# zx81_kbd_v0_4.net
KiCad netlist of a schematic drawn in EAGLE
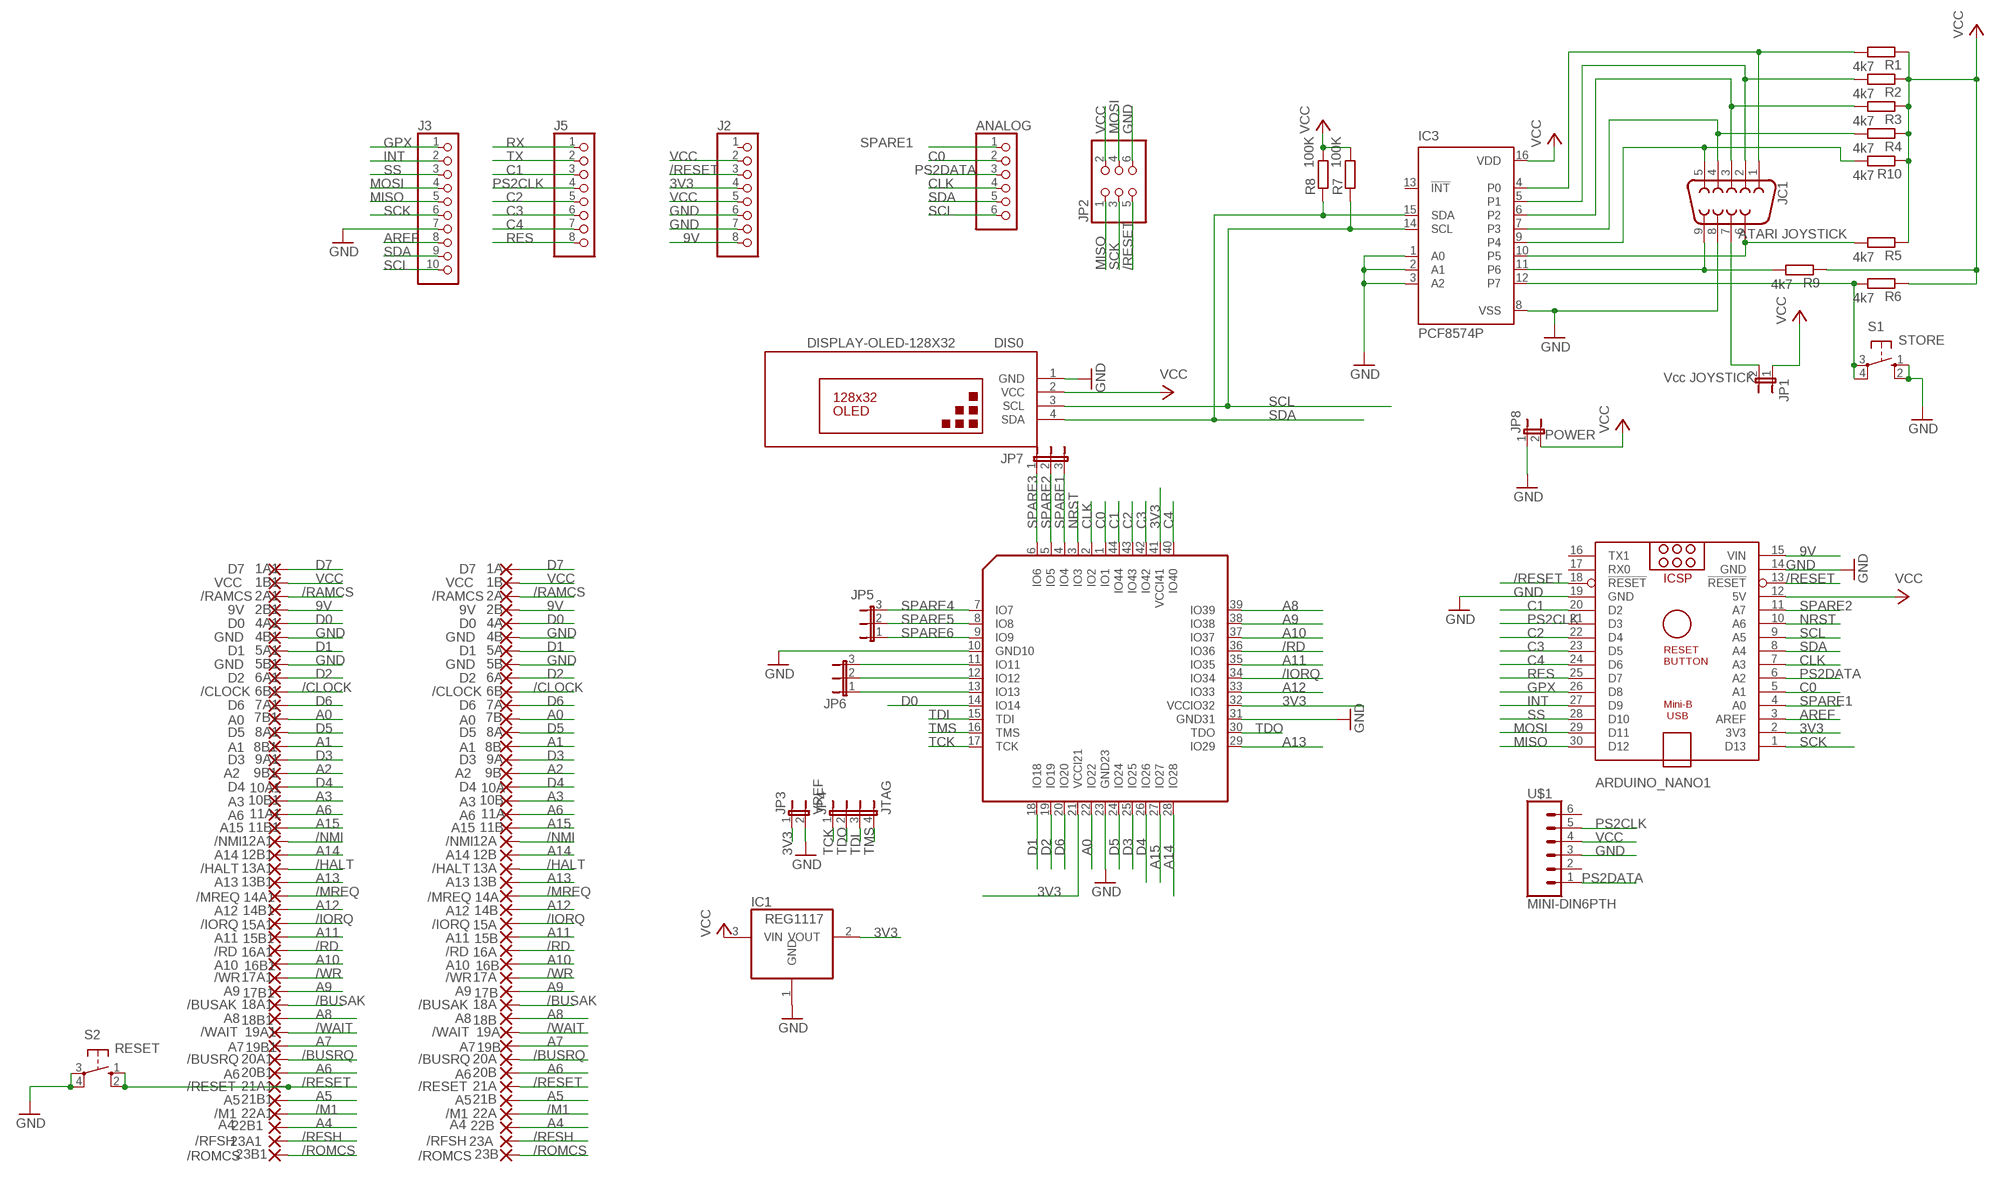
[diagram p0: schematic, sheet 1]

(export (version "E")
  (design (tool "Eeschema 10.0.6"))
  (components
    (comp (ref "1A")
      (value "D7")
      (footprint "eagle-import:EDGEPIN")
      (libsource (lib "eagle-import") (part "SMD2EDGEPIN"))
    )
    (comp (ref "1A1")
      (value "D7")
      (footprint "eagle-import:EDGEPIN")
      (libsource (lib "eagle-import") (part "SMD2EDGEPIN"))
    )
    (comp (ref "1B")
      (value "VCC")
      (footprint "eagle-import:EDGEPIN")
      (libsource (lib "eagle-import") (part "SMD2EDGEPIN"))
    )
    (comp (ref "1B1")
      (value "VCC")
      (footprint "eagle-import:EDGEPIN")
      (libsource (lib "eagle-import") (part "SMD2EDGEPIN"))
    )
    (comp (ref "2A")
      (value "/RAMCS")
      (footprint "eagle-import:EDGEPIN")
      (libsource (lib "eagle-import") (part "SMD2EDGEPIN"))
    )
    (comp (ref "2A1")
      (value "/RAMCS")
      (footprint "eagle-import:EDGEPIN")
      (libsource (lib "eagle-import") (part "SMD2EDGEPIN"))
    )
    (comp (ref "2B")
      (value "9V")
      (footprint "eagle-import:EDGEPIN")
      (libsource (lib "eagle-import") (part "SMD2EDGEPIN"))
    )
    (comp (ref "2B1")
      (value "9V")
      (footprint "eagle-import:EDGEPIN")
      (libsource (lib "eagle-import") (part "SMD2EDGEPIN"))
    )
    (comp (ref "4A")
      (value "D0")
      (footprint "eagle-import:EDGEPIN")
      (libsource (lib "eagle-import") (part "SMD2EDGEPIN"))
    )
    (comp (ref "4A1")
      (value "D0")
      (footprint "eagle-import:EDGEPIN")
      (libsource (lib "eagle-import") (part "SMD2EDGEPIN"))
    )
    (comp (ref "4B")
      (value "GND")
      (footprint "eagle-import:EDGEPIN")
      (libsource (lib "eagle-import") (part "SMD2EDGEPIN"))
    )
    (comp (ref "4B1")
      (value "GND")
      (footprint "eagle-import:EDGEPIN")
      (libsource (lib "eagle-import") (part "SMD2EDGEPIN"))
    )
    (comp (ref "5A")
      (value "D1")
      (footprint "eagle-import:EDGEPIN")
      (libsource (lib "eagle-import") (part "SMD2EDGEPIN"))
    )
    (comp (ref "5A1")
      (value "D1")
      (footprint "eagle-import:EDGEPIN")
      (libsource (lib "eagle-import") (part "SMD2EDGEPIN"))
    )
    (comp (ref "5B")
      (value "GND")
      (footprint "eagle-import:EDGEPIN")
      (libsource (lib "eagle-import") (part "SMD2EDGEPIN"))
    )
    (comp (ref "5B1")
      (value "GND")
      (footprint "eagle-import:EDGEPIN")
      (libsource (lib "eagle-import") (part "SMD2EDGEPIN"))
    )
    (comp (ref "6A")
      (value "D2")
      (footprint "eagle-import:EDGEPIN")
      (libsource (lib "eagle-import") (part "SMD2EDGEPIN"))
    )
    (comp (ref "6A1")
      (value "D2")
      (footprint "eagle-import:EDGEPIN")
      (libsource (lib "eagle-import") (part "SMD2EDGEPIN"))
    )
    (comp (ref "6B")
      (value "/CLOCK")
      (footprint "eagle-import:EDGEPIN")
      (libsource (lib "eagle-import") (part "SMD2EDGEPIN"))
    )
    (comp (ref "6B1")
      (value "/CLOCK")
      (footprint "eagle-import:EDGEPIN")
      (libsource (lib "eagle-import") (part "SMD2EDGEPIN"))
    )
    (comp (ref "7A")
      (value "D6")
      (footprint "eagle-import:EDGEPIN")
      (libsource (lib "eagle-import") (part "SMD2EDGEPIN"))
    )
    (comp (ref "7A1")
      (value "D6")
      (footprint "eagle-import:EDGEPIN")
      (libsource (lib "eagle-import") (part "SMD2EDGEPIN"))
    )
    (comp (ref "7B")
      (value "A0")
      (footprint "eagle-import:EDGEPIN")
      (libsource (lib "eagle-import") (part "SMD2EDGEPIN"))
    )
    (comp (ref "7B1")
      (value "A0")
      (footprint "eagle-import:EDGEPIN")
      (libsource (lib "eagle-import") (part "SMD2EDGEPIN"))
    )
    (comp (ref "8A")
      (value "D5")
      (footprint "eagle-import:EDGEPIN")
      (libsource (lib "eagle-import") (part "SMD2EDGEPIN"))
    )
    (comp (ref "8A1")
      (value "D5")
      (footprint "eagle-import:EDGEPIN")
      (libsource (lib "eagle-import") (part "SMD2EDGEPIN"))
    )
    (comp (ref "8B")
      (value "A1")
      (footprint "eagle-import:EDGEPIN")
      (libsource (lib "eagle-import") (part "SMD2EDGEPIN"))
    )
    (comp (ref "8B1")
      (value "A1")
      (footprint "eagle-import:EDGEPIN")
      (libsource (lib "eagle-import") (part "SMD2EDGEPIN"))
    )
    (comp (ref "9A")
      (value "D3")
      (footprint "eagle-import:EDGEPIN")
      (libsource (lib "eagle-import") (part "SMD2EDGEPIN"))
    )
    (comp (ref "9A1")
      (value "D3")
      (footprint "eagle-import:EDGEPIN")
      (libsource (lib "eagle-import") (part "SMD2EDGEPIN"))
    )
    (comp (ref "9B")
      (value "A2")
      (footprint "eagle-import:EDGEPIN")
      (libsource (lib "eagle-import") (part "SMD2EDGEPIN"))
    )
    (comp (ref "9B1")
      (value "A2")
      (footprint "eagle-import:EDGEPIN")
      (libsource (lib "eagle-import") (part "SMD2EDGEPIN"))
    )
    (comp (ref "10A")
      (value "D4")
      (footprint "eagle-import:EDGEPIN")
      (libsource (lib "eagle-import") (part "SMD2EDGEPIN"))
    )
    (comp (ref "10A1")
      (value "D4")
      (footprint "eagle-import:EDGEPIN")
      (libsource (lib "eagle-import") (part "SMD2EDGEPIN"))
    )
    (comp (ref "10B")
      (value "A3")
      (footprint "eagle-import:EDGEPIN")
      (libsource (lib "eagle-import") (part "SMD2EDGEPIN"))
    )
    (comp (ref "10B1")
      (value "A3")
      (footprint "eagle-import:EDGEPIN")
      (libsource (lib "eagle-import") (part "SMD2EDGEPIN"))
    )
    (comp (ref "11A")
      (value "A6")
      (footprint "eagle-import:EDGEPIN")
      (libsource (lib "eagle-import") (part "SMD2EDGEPIN"))
    )
    (comp (ref "11A1")
      (value "A6")
      (footprint "eagle-import:EDGEPIN")
      (libsource (lib "eagle-import") (part "SMD2EDGEPIN"))
    )
    (comp (ref "11B")
      (value "A15")
      (footprint "eagle-import:EDGEPIN")
      (libsource (lib "eagle-import") (part "SMD2EDGEPIN"))
    )
    (comp (ref "11B1")
      (value "A15")
      (footprint "eagle-import:EDGEPIN")
      (libsource (lib "eagle-import") (part "SMD2EDGEPIN"))
    )
    (comp (ref "12A")
      (value "/NMI")
      (footprint "eagle-import:EDGEPIN")
      (libsource (lib "eagle-import") (part "SMD2EDGEPIN"))
    )
    (comp (ref "12A1")
      (value "/NMI")
      (footprint "eagle-import:EDGEPIN")
      (libsource (lib "eagle-import") (part "SMD2EDGEPIN"))
    )
    (comp (ref "12B")
      (value "A14")
      (footprint "eagle-import:EDGEPIN")
      (libsource (lib "eagle-import") (part "SMD2EDGEPIN"))
    )
    (comp (ref "12B1")
      (value "A14")
      (footprint "eagle-import:EDGEPIN")
      (libsource (lib "eagle-import") (part "SMD2EDGEPIN"))
    )
    (comp (ref "13A")
      (value "/HALT")
      (footprint "eagle-import:EDGEPIN")
      (libsource (lib "eagle-import") (part "SMD2EDGEPIN"))
    )
    (comp (ref "13A1")
      (value "/HALT")
      (footprint "eagle-import:EDGEPIN")
      (libsource (lib "eagle-import") (part "SMD2EDGEPIN"))
    )
    (comp (ref "13B")
      (value "A13")
      (footprint "eagle-import:EDGEPIN")
      (libsource (lib "eagle-import") (part "SMD2EDGEPIN"))
    )
    (comp (ref "13B1")
      (value "A13")
      (footprint "eagle-import:EDGEPIN")
      (libsource (lib "eagle-import") (part "SMD2EDGEPIN"))
    )
    (comp (ref "14A")
      (value "/MREQ")
      (footprint "eagle-import:EDGEPIN")
      (libsource (lib "eagle-import") (part "SMD2EDGEPIN"))
    )
    (comp (ref "14A1")
      (value "/MREQ")
      (footprint "eagle-import:EDGEPIN")
      (libsource (lib "eagle-import") (part "SMD2EDGEPIN"))
    )
    (comp (ref "14B")
      (value "A12")
      (footprint "eagle-import:EDGEPIN")
      (libsource (lib "eagle-import") (part "SMD2EDGEPIN"))
    )
    (comp (ref "14B1")
      (value "A12")
      (footprint "eagle-import:EDGEPIN")
      (libsource (lib "eagle-import") (part "SMD2EDGEPIN"))
    )
    (comp (ref "15A")
      (value "/IORQ")
      (footprint "eagle-import:EDGEPIN")
      (libsource (lib "eagle-import") (part "SMD2EDGEPIN"))
    )
    (comp (ref "15A1")
      (value "/IORQ")
      (footprint "eagle-import:EDGEPIN")
      (libsource (lib "eagle-import") (part "SMD2EDGEPIN"))
    )
    (comp (ref "15B")
      (value "A11")
      (footprint "eagle-import:EDGEPIN")
      (libsource (lib "eagle-import") (part "SMD2EDGEPIN"))
    )
    (comp (ref "15B1")
      (value "A11")
      (footprint "eagle-import:EDGEPIN")
      (libsource (lib "eagle-import") (part "SMD2EDGEPIN"))
    )
    (comp (ref "16A")
      (value "/RD")
      (footprint "eagle-import:EDGEPIN")
      (libsource (lib "eagle-import") (part "SMD2EDGEPIN"))
    )
    (comp (ref "16A1")
      (value "/RD")
      (footprint "eagle-import:EDGEPIN")
      (libsource (lib "eagle-import") (part "SMD2EDGEPIN"))
    )
    (comp (ref "16B")
      (value "A10")
      (footprint "eagle-import:EDGEPIN")
      (libsource (lib "eagle-import") (part "SMD2EDGEPIN"))
    )
    (comp (ref "16B1")
      (value "A10")
      (footprint "eagle-import:EDGEPIN")
      (libsource (lib "eagle-import") (part "SMD2EDGEPIN"))
    )
    (comp (ref "17A")
      (value "/WR")
      (footprint "eagle-import:EDGEPIN")
      (libsource (lib "eagle-import") (part "SMD2EDGEPIN"))
    )
    (comp (ref "17A1")
      (value "/WR")
      (footprint "eagle-import:EDGEPIN")
      (libsource (lib "eagle-import") (part "SMD2EDGEPIN"))
    )
    (comp (ref "17B")
      (value "A9")
      (footprint "eagle-import:EDGEPIN")
      (libsource (lib "eagle-import") (part "SMD2EDGEPIN"))
    )
    (comp (ref "17B1")
      (value "A9")
      (footprint "eagle-import:EDGEPIN")
      (libsource (lib "eagle-import") (part "SMD2EDGEPIN"))
    )
    (comp (ref "18A")
      (value "/BUSAK")
      (footprint "eagle-import:EDGEPIN")
      (libsource (lib "eagle-import") (part "SMD2EDGEPIN"))
    )
    (comp (ref "18A1")
      (value "/BUSAK")
      (footprint "eagle-import:EDGEPIN")
      (libsource (lib "eagle-import") (part "SMD2EDGEPIN"))
    )
    (comp (ref "18B")
      (value "A8")
      (footprint "eagle-import:EDGEPIN")
      (libsource (lib "eagle-import") (part "SMD2EDGEPIN"))
    )
    (comp (ref "18B1")
      (value "A8")
      (footprint "eagle-import:EDGEPIN")
      (libsource (lib "eagle-import") (part "SMD2EDGEPIN"))
    )
    (comp (ref "19A")
      (value "/WAIT")
      (footprint "eagle-import:EDGEPIN")
      (libsource (lib "eagle-import") (part "SMD2EDGEPIN"))
    )
    (comp (ref "19A1")
      (value "/WAIT")
      (footprint "eagle-import:EDGEPIN")
      (libsource (lib "eagle-import") (part "SMD2EDGEPIN"))
    )
    (comp (ref "19B")
      (value "A7")
      (footprint "eagle-import:EDGEPIN")
      (libsource (lib "eagle-import") (part "SMD2EDGEPIN"))
    )
    (comp (ref "19B1")
      (value "A7")
      (footprint "eagle-import:EDGEPIN")
      (libsource (lib "eagle-import") (part "SMD2EDGEPIN"))
    )
    (comp (ref "20A")
      (value "/BUSRQ")
      (footprint "eagle-import:EDGEPIN")
      (libsource (lib "eagle-import") (part "SMD2EDGEPIN"))
    )
    (comp (ref "20A1")
      (value "/BUSRQ")
      (footprint "eagle-import:EDGEPIN")
      (libsource (lib "eagle-import") (part "SMD2EDGEPIN"))
    )
    (comp (ref "20B")
      (value "A6")
      (footprint "eagle-import:EDGEPIN")
      (libsource (lib "eagle-import") (part "SMD2EDGEPIN"))
    )
    (comp (ref "20B1")
      (value "A6")
      (footprint "eagle-import:EDGEPIN")
      (libsource (lib "eagle-import") (part "SMD2EDGEPIN"))
    )
    (comp (ref "21A")
      (value "/RESET")
      (footprint "eagle-import:EDGEPIN")
      (libsource (lib "eagle-import") (part "SMD2EDGEPIN"))
    )
    (comp (ref "21A1")
      (value "/RESET")
      (footprint "eagle-import:EDGEPIN")
      (libsource (lib "eagle-import") (part "SMD2EDGEPIN"))
    )
    (comp (ref "21B")
      (value "A5")
      (footprint "eagle-import:EDGEPIN")
      (libsource (lib "eagle-import") (part "SMD2EDGEPIN"))
    )
    (comp (ref "21B1")
      (value "A5")
      (footprint "eagle-import:EDGEPIN")
      (libsource (lib "eagle-import") (part "SMD2EDGEPIN"))
    )
    (comp (ref "22A")
      (value "/M1")
      (footprint "eagle-import:EDGEPIN")
      (libsource (lib "eagle-import") (part "SMD2EDGEPIN"))
    )
    (comp (ref "22A1")
      (value "/M1")
      (footprint "eagle-import:EDGEPIN")
      (libsource (lib "eagle-import") (part "SMD2EDGEPIN"))
    )
    (comp (ref "22B")
      (value "A4")
      (footprint "eagle-import:EDGEPIN")
      (libsource (lib "eagle-import") (part "SMD2EDGEPIN"))
    )
    (comp (ref "22B1")
      (value "A4")
      (footprint "eagle-import:EDGEPIN")
      (libsource (lib "eagle-import") (part "SMD2EDGEPIN"))
    )
    (comp (ref "23A")
      (value "/RFSH")
      (footprint "eagle-import:EDGEPIN")
      (libsource (lib "eagle-import") (part "SMD2EDGEPIN"))
    )
    (comp (ref "23A1")
      (value "/RFSH")
      (footprint "eagle-import:EDGEPIN")
      (libsource (lib "eagle-import") (part "SMD2EDGEPIN"))
    )
    (comp (ref "23B")
      (value "/ROMCS")
      (footprint "eagle-import:EDGEPIN")
      (libsource (lib "eagle-import") (part "SMD2EDGEPIN"))
    )
    (comp (ref "23B1")
      (value "/ROMCS")
      (footprint "eagle-import:EDGEPIN")
      (libsource (lib "eagle-import") (part "SMD2EDGEPIN"))
    )
    (comp (ref "ANALOG")
      (value "PINHD-1X6")
      (footprint "eagle-import:1X06")
      (libsource (lib "eagle-import") (part "PINHD-1X6"))
    )
    (comp (ref "ARDUINO_NANO1")
      (value "ARDUINO_NANO")
      (footprint "eagle-import:ARDUINO_NANO")
      (libsource (lib "eagle-import") (part "ARDUINO_NANO"))
    )
    (comp (ref "DIS0")
      (value "DISPLAY-OLED-128X32")
      (footprint "eagle-import:DISPLAY-OLED-128X32")
      (libsource (lib "eagle-import") (part "DISPLAY-OLED-128X32"))
    )
    (comp (ref "IC1")
      (value "REG1117")
      (footprint "eagle-import:SOT223")
      (libsource (lib "eagle-import") (part "REG1117"))
    )
    (comp (ref "IC3")
      (value "PCF8574P")
      (footprint "eagle-import:DIL16")
      (fields (field (name "MPN") "PCF8574PN"))
      (libsource (lib "eagle-import") (part "PCF8574P"))
    )
    (comp (ref "J2")
      (value "PINHD-1X8")
      (footprint "eagle-import:1X08")
      (libsource (lib "eagle-import") (part "PINHD-1X8"))
    )
    (comp (ref "J3")
      (value "PINHD-1X10")
      (footprint "eagle-import:1X10")
      (libsource (lib "eagle-import") (part "PINHD-1X10"))
    )
    (comp (ref "J5")
      (value "PINHD-1X8")
      (footprint "eagle-import:1X08")
      (libsource (lib "eagle-import") (part "PINHD-1X8"))
    )
    (comp (ref "JC1")
      (value "ATARI JOYSTICK")
      (footprint "eagle-import:DB9_MALE")
      (libsource (lib "eagle-import") (part "DB9MALE"))
    )
    (comp (ref "JP1")
      (value "Vcc JOYSTICK")
      (footprint "eagle-import:JP1")
      (libsource (lib "eagle-import") (part "JP1E"))
    )
    (comp (ref "JP2")
      (value "PINHD-2X3")
      (footprint "eagle-import:2X03")
      (libsource (lib "eagle-import") (part "PINHD-2X3"))
    )
    (comp (ref "JP3")
      (value "VREF")
      (footprint "eagle-import:JP1")
      (libsource (lib "eagle-import") (part "jumper_35741532_JP1E"))
    )
    (comp (ref "JP4")
      (value "JTAG")
      (footprint "eagle-import:JP4")
      (libsource (lib "eagle-import") (part "JP4E"))
    )
    (comp (ref "JP5")
      (value "JP2E")
      (footprint "eagle-import:JP2")
      (libsource (lib "eagle-import") (part "JP2E"))
    )
    (comp (ref "JP6")
      (value "JP2E")
      (footprint "eagle-import:JP2")
      (libsource (lib "eagle-import") (part "JP2E"))
    )
    (comp (ref "JP7")
      (value "JP2E")
      (footprint "eagle-import:JP2")
      (libsource (lib "eagle-import") (part "JP2E"))
    )
    (comp (ref "JP8")
      (value "POWER")
      (footprint "eagle-import:JP1")
      (libsource (lib "eagle-import") (part "JP1E"))
    )
    (comp (ref "R1")
      (value "4k7")
      (footprint "eagle-import:0204_7")
      (libsource (lib "eagle-import") (part "R-EU_0204/7"))
    )
    (comp (ref "R2")
      (value "4k7")
      (footprint "eagle-import:0204_7")
      (libsource (lib "eagle-import") (part "R-EU_0204/7"))
    )
    (comp (ref "R3")
      (value "4k7")
      (footprint "eagle-import:0204_7")
      (libsource (lib "eagle-import") (part "R-EU_0204/7"))
    )
    (comp (ref "R4")
      (value "4k7")
      (footprint "eagle-import:0204_7")
      (libsource (lib "eagle-import") (part "R-EU_0204/7"))
    )
    (comp (ref "R5")
      (value "4k7")
      (footprint "eagle-import:0204_7")
      (libsource (lib "eagle-import") (part "R-EU_0204/7"))
    )
    (comp (ref "R6")
      (value "4k7")
      (footprint "eagle-import:0204_7")
      (libsource (lib "eagle-import") (part "R-EU_0204/7"))
    )
    (comp (ref "R7")
      (value "100K")
      (footprint "eagle-import:0204_7")
      (libsource (lib "eagle-import") (part "R-EU_0204/7"))
    )
    (comp (ref "R8")
      (value "100K")
      (footprint "eagle-import:0204_7")
      (libsource (lib "eagle-import") (part "R-EU_0204/7"))
    )
    (comp (ref "R9")
      (value "4k7")
      (footprint "eagle-import:0204_7")
      (libsource (lib "eagle-import") (part "R-EU_0204/7"))
    )
    (comp (ref "R10")
      (value "4k7")
      (footprint "eagle-import:0204_7")
      (libsource (lib "eagle-import") (part "R-EU_0204/7"))
    )
    (comp (ref "S1")
      (value "STORE")
      (footprint "eagle-import:B3F-10XX_11MM")
      (libsource (lib "eagle-import") (part "10-XX11MM"))
    )
    (comp (ref "S2")
      (value "RESET")
      (footprint "eagle-import:B3F-10XX_11MM")
      (libsource (lib "eagle-import") (part "10-XX11MM"))
    )
    (comp (ref "U$1")
      (value "MINI-DIN6PTH")
      (footprint "eagle-import:MINI-DIN6")
      (libsource (lib "eagle-import") (part "MINI-DIN6PTH"))
    )
    (comp (ref "XC95CPLD")
      (value "XC9572PLC")
      (footprint "eagle-import:3M44")
      (libsource (lib "eagle-import") (part "XC9572PLC"))
    )
  )
  (nets
    (net (code "1") (name "/3V3") (class "Default")
      (node (ref "ARDUINO_NANO1") (pin "2") (pinfunction "3V3_2") (pintype "output"))
      (node (ref "IC1") (pin "2") (pinfunction "VOUT_2") (pintype "output"))
      (node (ref "J2") (pin "4") (pinfunction "4_4") (pintype "passive"))
      (node (ref "JP3") (pin "1") (pinfunction "1_1") (pintype "passive"))
      (node (ref "XC95CPLD") (pin "21") (pinfunction "VCCI21_21") (pintype "power_in"))
      (node (ref "XC95CPLD") (pin "32") (pinfunction "VCCIO32_32") (pintype "power_in"))
      (node (ref "XC95CPLD") (pin "41") (pinfunction "VCCI41_41") (pintype "power_in"))
    )
    (net (code "2") (name "/9V") (class "Default")
      (node (ref "2B") (pin "1") (pinfunction "P_1") (pintype "passive"))
      (node (ref "2B1") (pin "1") (pinfunction "P_1") (pintype "passive"))
      (node (ref "ARDUINO_NANO1") (pin "15") (pinfunction "VIN_15") (pintype "power_in"))
      (node (ref "J2") (pin "8") (pinfunction "8_8") (pintype "passive"))
    )
    (net (code "3") (name "/A0") (class "Default")
      (node (ref "7B") (pin "1") (pinfunction "P_1") (pintype "passive"))
      (node (ref "7B1") (pin "1") (pinfunction "P_1") (pintype "passive"))
      (node (ref "XC95CPLD") (pin "22") (pinfunction "IO22_22") (pintype "bidirectional"))
    )
    (net (code "4") (name "/A1") (class "Default")
      (node (ref "8B") (pin "1") (pinfunction "P_1") (pintype "passive"))
      (node (ref "8B1") (pin "1") (pinfunction "P_1") (pintype "passive"))
    )
    (net (code "5") (name "/A2") (class "Default")
      (node (ref "9B") (pin "1") (pinfunction "P_1") (pintype "passive"))
      (node (ref "9B1") (pin "1") (pinfunction "P_1") (pintype "passive"))
    )
    (net (code "6") (name "/A3") (class "Default")
      (node (ref "10B") (pin "1") (pinfunction "P_1") (pintype "passive"))
      (node (ref "10B1") (pin "1") (pinfunction "P_1") (pintype "passive"))
    )
    (net (code "7") (name "/A4") (class "Default")
      (node (ref "22B") (pin "1") (pinfunction "P_1") (pintype "passive"))
      (node (ref "22B1") (pin "1") (pinfunction "P_1") (pintype "passive"))
    )
    (net (code "8") (name "/A5") (class "Default")
      (node (ref "21B") (pin "1") (pinfunction "P_1") (pintype "passive"))
      (node (ref "21B1") (pin "1") (pinfunction "P_1") (pintype "passive"))
    )
    (net (code "9") (name "/A6") (class "Default")
      (node (ref "11A") (pin "1") (pinfunction "P_1") (pintype "passive"))
      (node (ref "11A1") (pin "1") (pinfunction "P_1") (pintype "passive"))
      (node (ref "20B") (pin "1") (pinfunction "P_1") (pintype "passive"))
      (node (ref "20B1") (pin "1") (pinfunction "P_1") (pintype "passive"))
    )
    (net (code "10") (name "/A7") (class "Default")
      (node (ref "19B") (pin "1") (pinfunction "P_1") (pintype "passive"))
      (node (ref "19B1") (pin "1") (pinfunction "P_1") (pintype "passive"))
    )
    (net (code "11") (name "/A8") (class "Default")
      (node (ref "18B") (pin "1") (pinfunction "P_1") (pintype "passive"))
      (node (ref "18B1") (pin "1") (pinfunction "P_1") (pintype "passive"))
      (node (ref "XC95CPLD") (pin "39") (pinfunction "IO39_39") (pintype "bidirectional"))
    )
    (net (code "12") (name "/A9") (class "Default")
      (node (ref "17B") (pin "1") (pinfunction "P_1") (pintype "passive"))
      (node (ref "17B1") (pin "1") (pinfunction "P_1") (pintype "passive"))
      (node (ref "XC95CPLD") (pin "38") (pinfunction "IO38_38") (pintype "bidirectional"))
    )
    (net (code "13") (name "/A10") (class "Default")
      (node (ref "16B") (pin "1") (pinfunction "P_1") (pintype "passive"))
      (node (ref "16B1") (pin "1") (pinfunction "P_1") (pintype "passive"))
      (node (ref "XC95CPLD") (pin "37") (pinfunction "IO37_37") (pintype "bidirectional"))
    )
    (net (code "14") (name "/A11") (class "Default")
      (node (ref "15B") (pin "1") (pinfunction "P_1") (pintype "passive"))
      (node (ref "15B1") (pin "1") (pinfunction "P_1") (pintype "passive"))
      (node (ref "XC95CPLD") (pin "35") (pinfunction "IO35_35") (pintype "bidirectional"))
    )
    (net (code "15") (name "/A12") (class "Default")
      (node (ref "14B") (pin "1") (pinfunction "P_1") (pintype "passive"))
      (node (ref "14B1") (pin "1") (pinfunction "P_1") (pintype "passive"))
      (node (ref "XC95CPLD") (pin "33") (pinfunction "IO33_33") (pintype "bidirectional"))
    )
    (net (code "16") (name "/A13") (class "Default")
      (node (ref "13B") (pin "1") (pinfunction "P_1") (pintype "passive"))
      (node (ref "13B1") (pin "1") (pinfunction "P_1") (pintype "passive"))
      (node (ref "XC95CPLD") (pin "29") (pinfunction "IO29_29") (pintype "bidirectional"))
    )
    (net (code "17") (name "/A14") (class "Default")
      (node (ref "12B") (pin "1") (pinfunction "P_1") (pintype "passive"))
      (node (ref "12B1") (pin "1") (pinfunction "P_1") (pintype "passive"))
      (node (ref "XC95CPLD") (pin "28") (pinfunction "IO28_28") (pintype "bidirectional"))
    )
    (net (code "18") (name "/A15") (class "Default")
      (node (ref "11B") (pin "1") (pinfunction "P_1") (pintype "passive"))
      (node (ref "11B1") (pin "1") (pinfunction "P_1") (pintype "passive"))
      (node (ref "XC95CPLD") (pin "27") (pinfunction "IO27_27") (pintype "bidirectional"))
    )
    (net (code "19") (name "/AREF") (class "Default")
      (node (ref "ARDUINO_NANO1") (pin "3") (pinfunction "AREF_3") (pintype "input"))
      (node (ref "J3") (pin "8") (pinfunction "8_8") (pintype "passive"))
    )
    (net (code "20") (name "/C0") (class "Default")
      (node (ref "ANALOG") (pin "2") (pinfunction "2_2") (pintype "passive"))
      (node (ref "ARDUINO_NANO1") (pin "5") (pinfunction "A1_5") (pintype "bidirectional"))
      (node (ref "XC95CPLD") (pin "1") (pinfunction "IO1_1") (pintype "bidirectional"))
    )
    (net (code "21") (name "/C1") (class "Default")
      (node (ref "ARDUINO_NANO1") (pin "20") (pinfunction "D2_20") (pintype "bidirectional"))
      (node (ref "J5") (pin "3") (pinfunction "3_3") (pintype "passive"))
      (node (ref "XC95CPLD") (pin "44") (pinfunction "IO44_44") (pintype "bidirectional"))
    )
    (net (code "22") (name "/C2") (class "Default")
      (node (ref "ARDUINO_NANO1") (pin "22") (pinfunction "D4_22") (pintype "bidirectional"))
      (node (ref "J5") (pin "5") (pinfunction "5_5") (pintype "passive"))
      (node (ref "XC95CPLD") (pin "43") (pinfunction "IO43_43") (pintype "bidirectional"))
    )
    (net (code "23") (name "/C3") (class "Default")
      (node (ref "ARDUINO_NANO1") (pin "23") (pinfunction "D5_23") (pintype "bidirectional"))
      (node (ref "J5") (pin "6") (pinfunction "6_6") (pintype "passive"))
      (node (ref "XC95CPLD") (pin "42") (pinfunction "IO42_42") (pintype "bidirectional"))
    )
    (net (code "24") (name "/C4") (class "Default")
      (node (ref "ARDUINO_NANO1") (pin "24") (pinfunction "D6_24") (pintype "bidirectional"))
      (node (ref "J5") (pin "7") (pinfunction "7_7") (pintype "passive"))
      (node (ref "XC95CPLD") (pin "40") (pinfunction "IO40_40") (pintype "bidirectional"))
    )
    (net (code "25") (name "/CLK") (class "Default")
      (node (ref "ANALOG") (pin "4") (pinfunction "4_4") (pintype "passive"))
      (node (ref "ARDUINO_NANO1") (pin "7") (pinfunction "A3_7") (pintype "bidirectional"))
      (node (ref "XC95CPLD") (pin "2") (pinfunction "IO2_2") (pintype "bidirectional"))
    )
    (net (code "26") (name "/D0") (class "Default")
      (node (ref "4A") (pin "1") (pinfunction "P_1") (pintype "passive"))
      (node (ref "4A1") (pin "1") (pinfunction "P_1") (pintype "passive"))
      (node (ref "XC95CPLD") (pin "14") (pinfunction "IO14_14") (pintype "bidirectional"))
    )
    (net (code "27") (name "/D1") (class "Default")
      (node (ref "5A") (pin "1") (pinfunction "P_1") (pintype "passive"))
      (node (ref "5A1") (pin "1") (pinfunction "P_1") (pintype "passive"))
      (node (ref "XC95CPLD") (pin "18") (pinfunction "IO18_18") (pintype "bidirectional"))
    )
    (net (code "28") (name "/D2") (class "Default")
      (node (ref "6A") (pin "1") (pinfunction "P_1") (pintype "passive"))
      (node (ref "6A1") (pin "1") (pinfunction "P_1") (pintype "passive"))
      (node (ref "XC95CPLD") (pin "19") (pinfunction "IO19_19") (pintype "bidirectional"))
    )
    (net (code "29") (name "/D3") (class "Default")
      (node (ref "9A") (pin "1") (pinfunction "P_1") (pintype "passive"))
      (node (ref "9A1") (pin "1") (pinfunction "P_1") (pintype "passive"))
      (node (ref "XC95CPLD") (pin "25") (pinfunction "IO25_25") (pintype "bidirectional"))
    )
    (net (code "30") (name "/D4") (class "Default")
      (node (ref "10A") (pin "1") (pinfunction "P_1") (pintype "passive"))
      (node (ref "10A1") (pin "1") (pinfunction "P_1") (pintype "passive"))
      (node (ref "XC95CPLD") (pin "26") (pinfunction "IO26_26") (pintype "bidirectional"))
    )
    (net (code "31") (name "/D5") (class "Default")
      (node (ref "8A") (pin "1") (pinfunction "P_1") (pintype "passive"))
      (node (ref "8A1") (pin "1") (pinfunction "P_1") (pintype "passive"))
      (node (ref "XC95CPLD") (pin "24") (pinfunction "IO24_24") (pintype "bidirectional"))
    )
    (net (code "32") (name "/D6") (class "Default")
      (node (ref "7A") (pin "1") (pinfunction "P_1") (pintype "passive"))
      (node (ref "7A1") (pin "1") (pinfunction "P_1") (pintype "passive"))
      (node (ref "XC95CPLD") (pin "20") (pinfunction "IO20_20") (pintype "bidirectional"))
    )
    (net (code "33") (name "/D7") (class "Default")
      (node (ref "1A") (pin "1") (pinfunction "P_1") (pintype "passive"))
      (node (ref "1A1") (pin "1") (pinfunction "P_1") (pintype "passive"))
    )
    (net (code "34") (name "/GPX") (class "Default")
      (node (ref "ARDUINO_NANO1") (pin "26") (pinfunction "D8_26") (pintype "bidirectional"))
      (node (ref "J3") (pin "1") (pinfunction "1_1") (pintype "passive"))
    )
    (net (code "35") (name "/INT") (class "Default")
      (node (ref "ARDUINO_NANO1") (pin "27") (pinfunction "D9_27") (pintype "bidirectional"))
      (node (ref "J3") (pin "2") (pinfunction "2_2") (pintype "passive"))
    )
    (net (code "36") (name "/MISO") (class "Default")
      (node (ref "ARDUINO_NANO1") (pin "30") (pinfunction "D12_30") (pintype "bidirectional"))
      (node (ref "J3") (pin "5") (pinfunction "5_5") (pintype "passive"))
      (node (ref "JP2") (pin "1") (pinfunction "1_1") (pintype "passive"))
    )
    (net (code "37") (name "/MOSI") (class "Default")
      (node (ref "ARDUINO_NANO1") (pin "29") (pinfunction "D11_29") (pintype "bidirectional"))
      (node (ref "J3") (pin "4") (pinfunction "4_4") (pintype "passive"))
      (node (ref "JP2") (pin "4") (pinfunction "4_4") (pintype "passive"))
    )
    (net (code "38") (name "/NRST") (class "Default")
      (node (ref "ARDUINO_NANO1") (pin "10") (pinfunction "A6_10") (pintype "bidirectional"))
      (node (ref "XC95CPLD") (pin "3") (pinfunction "IO3_3") (pintype "bidirectional"))
    )
    (net (code "39") (name "/PS2CLK") (class "Default")
      (node (ref "ARDUINO_NANO1") (pin "21") (pinfunction "D3_21") (pintype "bidirectional"))
      (node (ref "J5") (pin "4") (pinfunction "4_4") (pintype "passive"))
      (node (ref "U$1") (pin "5") (pinfunction "5_5") (pintype "passive"))
    )
    (net (code "40") (name "/PS2DATA") (class "Default")
      (node (ref "ANALOG") (pin "3") (pinfunction "3_3") (pintype "passive"))
      (node (ref "ARDUINO_NANO1") (pin "6") (pinfunction "A2_6") (pintype "bidirectional"))
      (node (ref "U$1") (pin "1") (pinfunction "1_1") (pintype "passive"))
    )
    (net (code "41") (name "/RES") (class "Default")
      (node (ref "ARDUINO_NANO1") (pin "25") (pinfunction "D7_25") (pintype "bidirectional"))
      (node (ref "J5") (pin "8") (pinfunction "8_8") (pintype "passive"))
    )
    (net (code "42") (name "/RX") (class "Default")
      (node (ref "J5") (pin "1") (pinfunction "1_1") (pintype "passive"))
    )
    (net (code "43") (name "/SCK") (class "Default")
      (node (ref "ARDUINO_NANO1") (pin "1") (pinfunction "D13_1") (pintype "bidirectional"))
      (node (ref "J3") (pin "6") (pinfunction "6_6") (pintype "passive"))
      (node (ref "JP2") (pin "3") (pinfunction "3_3") (pintype "passive"))
    )
    (net (code "44") (name "/SCL") (class "Default")
      (node (ref "ANALOG") (pin "6") (pinfunction "6_6") (pintype "passive"))
      (node (ref "ARDUINO_NANO1") (pin "9") (pinfunction "A5_9") (pintype "bidirectional"))
      (node (ref "DIS0") (pin "3") (pinfunction "SCL_3") (pintype "bidirectional"))
      (node (ref "IC3") (pin "14") (pinfunction "SCL_14") (pintype "input"))
      (node (ref "J3") (pin "10") (pinfunction "10_10") (pintype "passive"))
      (node (ref "R7") (pin "1") (pinfunction "1_1") (pintype "passive"))
    )
    (net (code "45") (name "/SDA") (class "Default")
      (node (ref "ANALOG") (pin "5") (pinfunction "5_5") (pintype "passive"))
      (node (ref "ARDUINO_NANO1") (pin "8") (pinfunction "A4_8") (pintype "bidirectional"))
      (node (ref "DIS0") (pin "4") (pinfunction "SDA_4") (pintype "bidirectional"))
      (node (ref "IC3") (pin "15") (pinfunction "SDA_15") (pintype "bidirectional"))
      (node (ref "J3") (pin "9") (pinfunction "9_9") (pintype "passive"))
      (node (ref "R8") (pin "1") (pinfunction "1_1") (pintype "passive"))
    )
    (net (code "46") (name "/SPARE1") (class "Default")
      (node (ref "ANALOG") (pin "1") (pinfunction "1_1") (pintype "passive"))
      (node (ref "ARDUINO_NANO1") (pin "4") (pinfunction "A0_4") (pintype "bidirectional"))
      (node (ref "JP7") (pin "3") (pinfunction "3_3") (pintype "passive"))
      (node (ref "XC95CPLD") (pin "4") (pinfunction "IO4_4") (pintype "bidirectional"))
    )
    (net (code "47") (name "/SPARE2") (class "Default")
      (node (ref "ARDUINO_NANO1") (pin "11") (pinfunction "A7_11") (pintype "bidirectional"))
      (node (ref "JP7") (pin "2") (pinfunction "2_2") (pintype "passive"))
      (node (ref "XC95CPLD") (pin "5") (pinfunction "IO5_5") (pintype "bidirectional"))
    )
    (net (code "48") (name "/SPARE3") (class "Default")
      (node (ref "JP7") (pin "1") (pinfunction "1_1") (pintype "passive"))
      (node (ref "XC95CPLD") (pin "6") (pinfunction "IO6_6") (pintype "bidirectional"))
    )
    (net (code "49") (name "/SPARE4") (class "Default")
      (node (ref "JP5") (pin "3") (pinfunction "3_3") (pintype "passive"))
      (node (ref "XC95CPLD") (pin "7") (pinfunction "IO7_7") (pintype "bidirectional"))
    )
    (net (code "50") (name "/SPARE5") (class "Default")
      (node (ref "JP5") (pin "2") (pinfunction "2_2") (pintype "passive"))
      (node (ref "XC95CPLD") (pin "8") (pinfunction "IO8_8") (pintype "bidirectional"))
    )
    (net (code "51") (name "/SPARE6") (class "Default")
      (node (ref "JP5") (pin "1") (pinfunction "1_1") (pintype "passive"))
      (node (ref "XC95CPLD") (pin "9") (pinfunction "IO9_9") (pintype "bidirectional"))
    )
    (net (code "52") (name "/SS") (class "Default")
      (node (ref "ARDUINO_NANO1") (pin "28") (pinfunction "D10_28") (pintype "bidirectional"))
      (node (ref "J3") (pin "3") (pinfunction "3_3") (pintype "passive"))
    )
    (net (code "53") (name "/TCK") (class "Default")
      (node (ref "JP4") (pin "1") (pinfunction "1_1") (pintype "passive"))
      (node (ref "XC95CPLD") (pin "17") (pinfunction "TCK_17") (pintype "passive"))
    )
    (net (code "54") (name "/TDI") (class "Default")
      (node (ref "JP4") (pin "3") (pinfunction "3_3") (pintype "passive"))
      (node (ref "XC95CPLD") (pin "15") (pinfunction "TDI_15") (pintype "passive"))
    )
    (net (code "55") (name "/TDO") (class "Default")
      (node (ref "JP4") (pin "2") (pinfunction "2_2") (pintype "passive"))
      (node (ref "XC95CPLD") (pin "30") (pinfunction "TDO_30") (pintype "passive"))
    )
    (net (code "56") (name "/TMS") (class "Default")
      (node (ref "JP4") (pin "4") (pinfunction "4_4") (pintype "passive"))
      (node (ref "XC95CPLD") (pin "16") (pinfunction "TMS_16") (pintype "passive"))
    )
    (net (code "57") (name "/TX") (class "Default")
      (node (ref "J5") (pin "2") (pinfunction "2_2") (pintype "passive"))
    )
    (net (code "58") (name "/{slash}BUSAK") (class "Default")
      (node (ref "18A") (pin "1") (pinfunction "P_1") (pintype "passive"))
      (node (ref "18A1") (pin "1") (pinfunction "P_1") (pintype "passive"))
    )
    (net (code "59") (name "/{slash}BUSRQ") (class "Default")
      (node (ref "20A") (pin "1") (pinfunction "P_1") (pintype "passive"))
      (node (ref "20A1") (pin "1") (pinfunction "P_1") (pintype "passive"))
    )
    (net (code "60") (name "/{slash}CLOCK") (class "Default")
      (node (ref "6B") (pin "1") (pinfunction "P_1") (pintype "passive"))
      (node (ref "6B1") (pin "1") (pinfunction "P_1") (pintype "passive"))
    )
    (net (code "61") (name "/{slash}HALT") (class "Default")
      (node (ref "13A") (pin "1") (pinfunction "P_1") (pintype "passive"))
      (node (ref "13A1") (pin "1") (pinfunction "P_1") (pintype "passive"))
    )
    (net (code "62") (name "/{slash}IORQ") (class "Default")
      (node (ref "15A") (pin "1") (pinfunction "P_1") (pintype "passive"))
      (node (ref "15A1") (pin "1") (pinfunction "P_1") (pintype "passive"))
      (node (ref "XC95CPLD") (pin "34") (pinfunction "IO34_34") (pintype "bidirectional"))
    )
    (net (code "63") (name "/{slash}M1") (class "Default")
      (node (ref "22A") (pin "1") (pinfunction "P_1") (pintype "passive"))
      (node (ref "22A1") (pin "1") (pinfunction "P_1") (pintype "passive"))
    )
    (net (code "64") (name "/{slash}MREQ") (class "Default")
      (node (ref "14A") (pin "1") (pinfunction "P_1") (pintype "passive"))
      (node (ref "14A1") (pin "1") (pinfunction "P_1") (pintype "passive"))
    )
    (net (code "65") (name "/{slash}NMI") (class "Default")
      (node (ref "12A") (pin "1") (pinfunction "P_1") (pintype "passive"))
      (node (ref "12A1") (pin "1") (pinfunction "P_1") (pintype "passive"))
    )
    (net (code "66") (name "/{slash}RAMCS") (class "Default")
      (node (ref "2A") (pin "1") (pinfunction "P_1") (pintype "passive"))
      (node (ref "2A1") (pin "1") (pinfunction "P_1") (pintype "passive"))
    )
    (net (code "67") (name "/{slash}RD") (class "Default")
      (node (ref "16A") (pin "1") (pinfunction "P_1") (pintype "passive"))
      (node (ref "16A1") (pin "1") (pinfunction "P_1") (pintype "passive"))
      (node (ref "XC95CPLD") (pin "36") (pinfunction "IO36_36") (pintype "bidirectional"))
    )
    (net (code "68") (name "/{slash}RESET") (class "Default")
      (node (ref "21A") (pin "1") (pinfunction "P_1") (pintype "passive"))
      (node (ref "21A1") (pin "1") (pinfunction "P_1") (pintype "passive"))
      (node (ref "ARDUINO_NANO1") (pin "13") (pinfunction "~{RESET}_13") (pintype "input"))
      (node (ref "ARDUINO_NANO1") (pin "18") (pinfunction "~{RESET}_18") (pintype "input"))
      (node (ref "J2") (pin "3") (pinfunction "3_3") (pintype "passive"))
      (node (ref "JP2") (pin "5") (pinfunction "5_5") (pintype "passive"))
      (node (ref "S2") (pin "1") (pinfunction "S_1") (pintype "passive"))
      (node (ref "S2") (pin "2") (pinfunction "S1_2") (pintype "passive"))
    )
    (net (code "69") (name "/{slash}RFSH") (class "Default")
      (node (ref "23A") (pin "1") (pinfunction "P_1") (pintype "passive"))
      (node (ref "23A1") (pin "1") (pinfunction "P_1") (pintype "passive"))
    )
    (net (code "70") (name "/{slash}ROMCS") (class "Default")
      (node (ref "23B") (pin "1") (pinfunction "P_1") (pintype "passive"))
      (node (ref "23B1") (pin "1") (pinfunction "P_1") (pintype "passive"))
    )
    (net (code "71") (name "/{slash}WAIT") (class "Default")
      (node (ref "19A") (pin "1") (pinfunction "P_1") (pintype "passive"))
      (node (ref "19A1") (pin "1") (pinfunction "P_1") (pintype "passive"))
    )
    (net (code "72") (name "/{slash}WR") (class "Default")
      (node (ref "17A") (pin "1") (pinfunction "P_1") (pintype "passive"))
      (node (ref "17A1") (pin "1") (pinfunction "P_1") (pintype "passive"))
    )
    (net (code "73") (name "GND") (class "Default")
      (node (ref "4B") (pin "1") (pinfunction "P_1") (pintype "passive"))
      (node (ref "4B1") (pin "1") (pinfunction "P_1") (pintype "passive"))
      (node (ref "5B") (pin "1") (pinfunction "P_1") (pintype "passive"))
      (node (ref "5B1") (pin "1") (pinfunction "P_1") (pintype "passive"))
      (node (ref "ARDUINO_NANO1") (pin "14") (pinfunction "GND_14") (pintype "power_in"))
      (node (ref "ARDUINO_NANO1") (pin "19") (pinfunction "GND_19") (pintype "power_in"))
      (node (ref "DIS0") (pin "1") (pinfunction "GND_1") (pintype "power_in"))
      (node (ref "IC1") (pin "1") (pinfunction "GND_1") (pintype "power_in"))
      (node (ref "IC3") (pin "1") (pinfunction "A0_1") (pintype "input"))
      (node (ref "IC3") (pin "2") (pinfunction "A1_2") (pintype "input"))
      (node (ref "IC3") (pin "3") (pinfunction "A2_3") (pintype "input"))
      (node (ref "IC3") (pin "8") (pinfunction "VSS_8") (pintype "power_in"))
      (node (ref "J2") (pin "6") (pinfunction "6_6") (pintype "passive"))
      (node (ref "J2") (pin "7") (pinfunction "7_7") (pintype "passive"))
      (node (ref "J3") (pin "7") (pinfunction "7_7") (pintype "passive"))
      (node (ref "JC1") (pin "8") (pinfunction "8_8") (pintype "passive"))
      (node (ref "JP2") (pin "6") (pinfunction "6_6") (pintype "passive"))
      (node (ref "JP3") (pin "2") (pinfunction "2_2") (pintype "passive"))
      (node (ref "JP8") (pin "1") (pinfunction "1_1") (pintype "passive"))
      (node (ref "S1") (pin "1") (pinfunction "S_1") (pintype "passive"))
      (node (ref "S1") (pin "2") (pinfunction "S1_2") (pintype "passive"))
      (node (ref "S2") (pin "3") (pinfunction "P_3") (pintype "passive"))
      (node (ref "S2") (pin "4") (pinfunction "P1_4") (pintype "passive"))
      (node (ref "U$1") (pin "3") (pinfunction "3_3") (pintype "passive"))
      (node (ref "XC95CPLD") (pin "10") (pinfunction "GND10_10") (pintype "power_in"))
      (node (ref "XC95CPLD") (pin "23") (pinfunction "GND23_23") (pintype "power_in"))
      (node (ref "XC95CPLD") (pin "31") (pinfunction "GND31_31") (pintype "power_in"))
    )
    (net (code "74") (name "Net-(IC3-P0)") (class "Default")
      (node (ref "IC3") (pin "4") (pinfunction "P0_4") (pintype "bidirectional"))
      (node (ref "JC1") (pin "1") (pinfunction "1_1") (pintype "passive"))
      (node (ref "R1") (pin "2") (pinfunction "2_2") (pintype "passive"))
    )
    (net (code "75") (name "Net-(IC3-P1)") (class "Default")
      (node (ref "IC3") (pin "5") (pinfunction "P1_5") (pintype "bidirectional"))
      (node (ref "JC1") (pin "2") (pinfunction "2_2") (pintype "passive"))
      (node (ref "R2") (pin "2") (pinfunction "2_2") (pintype "passive"))
    )
    (net (code "76") (name "Net-(IC3-P2)") (class "Default")
      (node (ref "IC3") (pin "6") (pinfunction "P2_6") (pintype "bidirectional"))
      (node (ref "JC1") (pin "3") (pinfunction "3_3") (pintype "passive"))
      (node (ref "R3") (pin "2") (pinfunction "2_2") (pintype "passive"))
    )
    (net (code "77") (name "Net-(IC3-P3)") (class "Default")
      (node (ref "IC3") (pin "7") (pinfunction "P3_7") (pintype "bidirectional"))
      (node (ref "JC1") (pin "4") (pinfunction "4_4") (pintype "passive"))
      (node (ref "R4") (pin "2") (pinfunction "2_2") (pintype "passive"))
    )
    (net (code "78") (name "Net-(IC3-P4)") (class "Default")
      (node (ref "IC3") (pin "9") (pinfunction "P4_9") (pintype "bidirectional"))
      (node (ref "JC1") (pin "5") (pinfunction "5_5") (pintype "passive"))
      (node (ref "R10") (pin "2") (pinfunction "2_2") (pintype "passive"))
    )
    (net (code "79") (name "Net-(IC3-P5)") (class "Default")
      (node (ref "IC3") (pin "10") (pinfunction "P5_10") (pintype "bidirectional"))
      (node (ref "JC1") (pin "6") (pinfunction "6_6") (pintype "passive"))
      (node (ref "R5") (pin "2") (pinfunction "2_2") (pintype "passive"))
    )
    (net (code "80") (name "Net-(IC3-P6)") (class "Default")
      (node (ref "IC3") (pin "11") (pinfunction "P6_11") (pintype "bidirectional"))
      (node (ref "JC1") (pin "9") (pinfunction "9_9") (pintype "passive"))
      (node (ref "R9") (pin "2") (pinfunction "2_2") (pintype "passive"))
    )
    (net (code "81") (name "Net-(IC3-P7)") (class "Default")
      (node (ref "IC3") (pin "12") (pinfunction "P7_12") (pintype "bidirectional"))
      (node (ref "R6") (pin "2") (pinfunction "2_2") (pintype "passive"))
      (node (ref "S1") (pin "3") (pinfunction "P_3") (pintype "passive"))
      (node (ref "S1") (pin "4") (pinfunction "P1_4") (pintype "passive"))
    )
    (net (code "82") (name "Net-(JC1-Pad7)") (class "Default")
      (node (ref "JC1") (pin "7") (pinfunction "7_7") (pintype "passive"))
      (node (ref "JP1") (pin "2") (pinfunction "2_2") (pintype "passive"))
    )
    (net (code "83") (name "Net-(XC95CPLD-IO11)") (class "Default")
      (node (ref "JP6") (pin "3") (pinfunction "3_3") (pintype "passive"))
      (node (ref "XC95CPLD") (pin "11") (pinfunction "IO11_11") (pintype "bidirectional"))
    )
    (net (code "84") (name "Net-(XC95CPLD-IO12)") (class "Default")
      (node (ref "JP6") (pin "2") (pinfunction "2_2") (pintype "passive"))
      (node (ref "XC95CPLD") (pin "12") (pinfunction "IO12_12") (pintype "bidirectional"))
    )
    (net (code "85") (name "Net-(XC95CPLD-IO13)") (class "Default")
      (node (ref "JP6") (pin "1") (pinfunction "1_1") (pintype "passive"))
      (node (ref "XC95CPLD") (pin "13") (pinfunction "IO13_13") (pintype "bidirectional"))
    )
    (net (code "86") (name "VCC") (class "Default")
      (node (ref "1B") (pin "1") (pinfunction "P_1") (pintype "passive"))
      (node (ref "1B1") (pin "1") (pinfunction "P_1") (pintype "passive"))
      (node (ref "ARDUINO_NANO1") (pin "12") (pinfunction "5V_12") (pintype "power_in"))
      (node (ref "DIS0") (pin "2") (pinfunction "VCC_2") (pintype "power_in"))
      (node (ref "IC1") (pin "3") (pinfunction "VIN_3") (pintype "input"))
      (node (ref "IC3") (pin "16") (pinfunction "VDD_16") (pintype "power_in"))
      (node (ref "J2") (pin "2") (pinfunction "2_2") (pintype "passive"))
      (node (ref "J2") (pin "5") (pinfunction "5_5") (pintype "passive"))
      (node (ref "JP1") (pin "1") (pinfunction "1_1") (pintype "passive"))
      (node (ref "JP2") (pin "2") (pinfunction "2_2") (pintype "passive"))
      (node (ref "JP8") (pin "2") (pinfunction "2_2") (pintype "passive"))
      (node (ref "R1") (pin "1") (pinfunction "1_1") (pintype "passive"))
      (node (ref "R10") (pin "1") (pinfunction "1_1") (pintype "passive"))
      (node (ref "R2") (pin "1") (pinfunction "1_1") (pintype "passive"))
      (node (ref "R3") (pin "1") (pinfunction "1_1") (pintype "passive"))
      (node (ref "R4") (pin "1") (pinfunction "1_1") (pintype "passive"))
      (node (ref "R5") (pin "1") (pinfunction "1_1") (pintype "passive"))
      (node (ref "R6") (pin "1") (pinfunction "1_1") (pintype "passive"))
      (node (ref "R7") (pin "2") (pinfunction "2_2") (pintype "passive"))
      (node (ref "R8") (pin "2") (pinfunction "2_2") (pintype "passive"))
      (node (ref "R9") (pin "1") (pinfunction "1_1") (pintype "passive"))
      (node (ref "U$1") (pin "4") (pinfunction "4_4") (pintype "passive"))
    )
    (net (code "87") (name "unconnected-(ARDUINO_NANO1-RX0-Pad17)") (class "Default")
      (node (ref "ARDUINO_NANO1") (pin "17") (pinfunction "RX0_17") (pintype "bidirectional"))
    )
    (net (code "88") (name "unconnected-(ARDUINO_NANO1-TX1-Pad16)") (class "Default")
      (node (ref "ARDUINO_NANO1") (pin "16") (pinfunction "TX1_16") (pintype "bidirectional"))
    )
    (net (code "89") (name "unconnected-(IC3-~{INT}-Pad13)") (class "Default")
      (node (ref "IC3") (pin "13") (pinfunction "~{INT}_13") (pintype "output"))
    )
    (net (code "90") (name "unconnected-(J2-Pad1)") (class "Default")
      (node (ref "J2") (pin "1") (pinfunction "1_1") (pintype "passive"))
    )
    (net (code "91") (name "unconnected-(U$1-Pad2)") (class "Default")
      (node (ref "U$1") (pin "2") (pinfunction "2_2") (pintype "passive"))
    )
    (net (code "92") (name "unconnected-(U$1-Pad6)") (class "Default")
      (node (ref "U$1") (pin "6") (pinfunction "6_6") (pintype "passive"))
    )
  )
)
